# Power_Sheet.net
KiCad netlist of a schematic drawn in Altium Designer
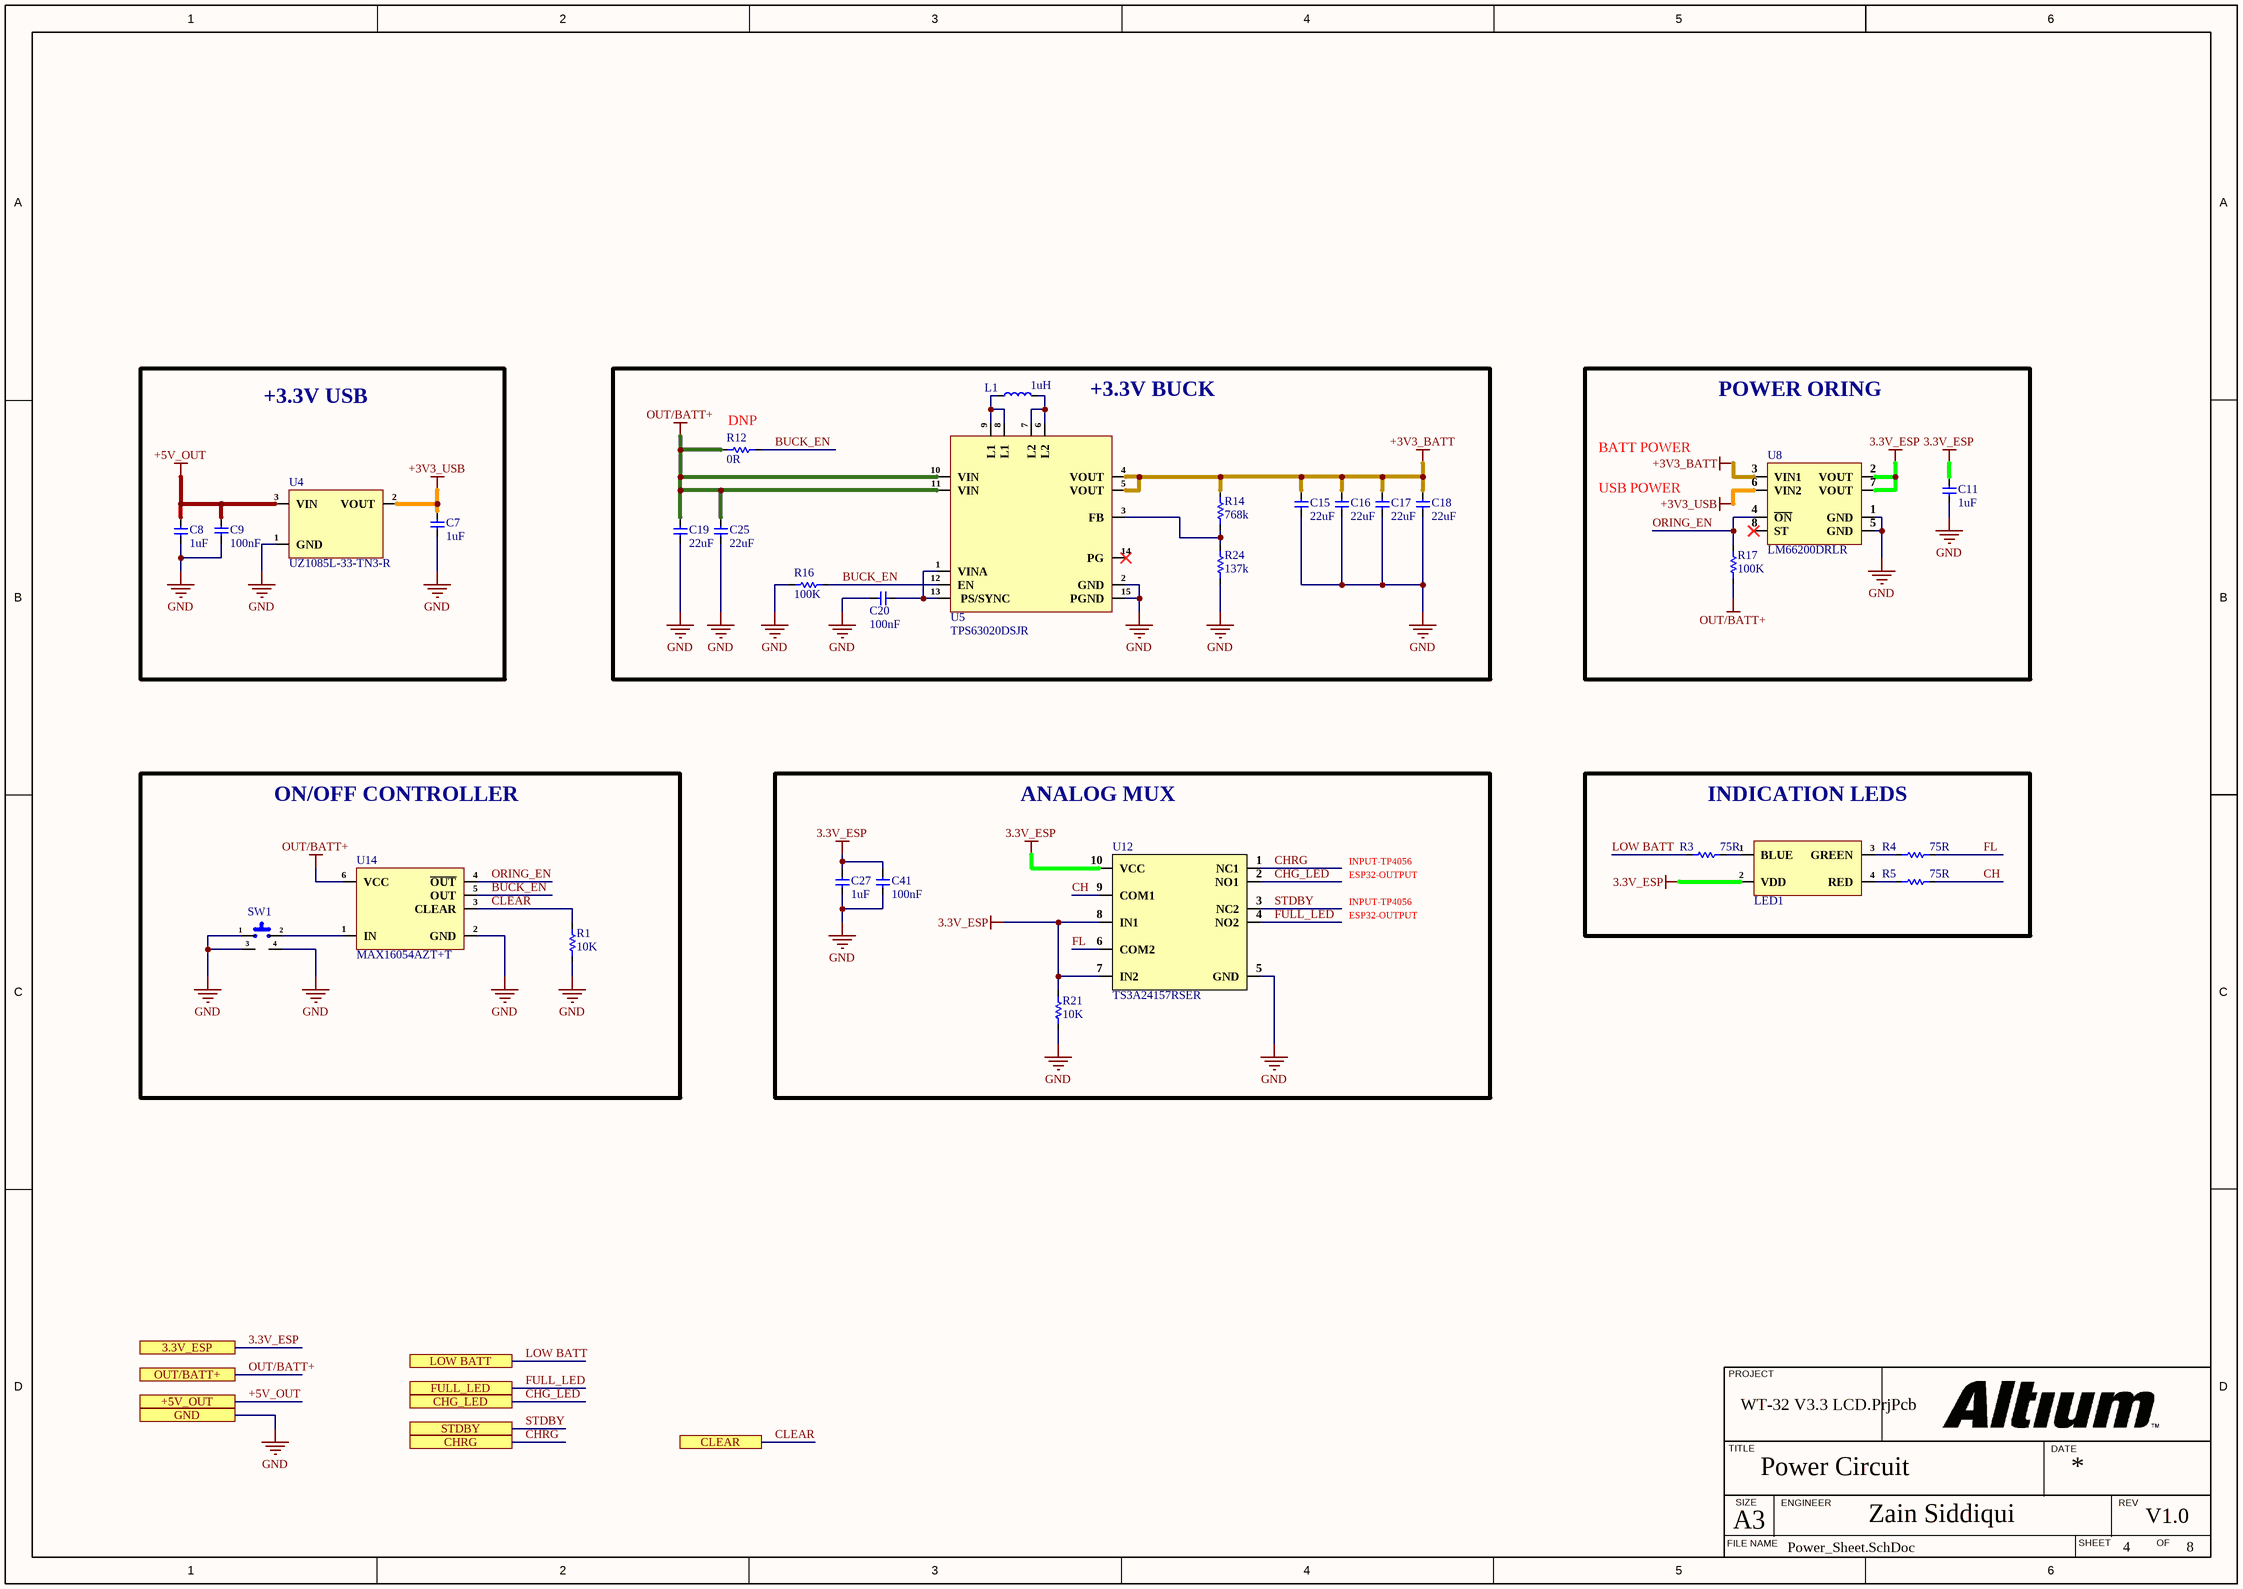
[diagram p0: Power_Sheet.SchDoc]

(export (version "E")
  (design (tool "Eeschema 10.0.6"))
  (components
    (comp (ref "C7")
      (value "1uF")
      (footprint "Cap-0402")
      (description "CAP CER 1UF 10V X5R 0402")
      (fields
        (field (name "MANUFACTURER") "Yageo")
        (field (name "MANUFACTURER PART NUMBER") "CC0402KRX5R6BB105")
      )
      (libsource (lib "eSpark Libraries") (part "CC0402KRX5R6BB105"))
    )
    (comp (ref "C8")
      (value "1uF")
      (footprint "Cap-0402")
      (description "CAP CER 1UF 25V X5R 0402")
      (fields
        (field (name "MANUFACTURER") "Yageo")
        (field (name "MANUFACTURER PART NUMBER") "CC0402KRX5R8BB105")
      )
      (libsource (lib "eSpark Libraries") (part "CC0402KRX5R8BB105"))
    )
    (comp (ref "C9")
      (value "100nF")
      (footprint "cap-0402")
      (description "CAP CER 0.1UF 50V X7R 0402")
      (fields
        (field (name "MANUFACTURER") "TDK")
        (field (name "MANUFACTURER PART NUMBER") "C1005X7R1H104KT000F")
      )
      (libsource (lib "eSpark Libraries") (part "C1005X7R1H104KT000F"))
    )
    (comp (ref "C11")
      (value "1uF")
      (footprint "Cap-0402")
      (description "CAP CER 1UF 25V X5R 0402")
      (fields
        (field (name "MANUFACTURER") "Yageo")
        (field (name "MANUFACTURER PART NUMBER") "CC0402KRX5R8BB105")
      )
      (libsource (lib "eSpark Libraries") (part "CC0402KRX5R8BB105"))
    )
    (comp (ref "C15")
      (value "22uF")
      (footprint "Cap-0805")
      (description "CAP CER 22UF 35V X5R 0805")
      (fields
        (field (name "MANUFACTURER") "TDK Corporation")
        (field (name "MANUFACTURER PART NUMBER") "C2012X5R1V226MT000E")
      )
      (libsource (lib "eSpark Libraries") (part "C2012X5R1V226MT000E"))
    )
    (comp (ref "C16")
      (value "22uF")
      (footprint "Cap-0805")
      (description "CAP CER 22UF 35V X5R 0805")
      (fields
        (field (name "MANUFACTURER") "TDK Corporation")
        (field (name "MANUFACTURER PART NUMBER") "C2012X5R1V226MT000E")
      )
      (libsource (lib "eSpark Libraries") (part "C2012X5R1V226MT000E"))
    )
    (comp (ref "C17")
      (value "22uF")
      (footprint "Cap-0805")
      (description "CAP CER 22UF 35V X5R 0805")
      (fields
        (field (name "MANUFACTURER") "TDK Corporation")
        (field (name "MANUFACTURER PART NUMBER") "C2012X5R1V226MT000E")
      )
      (libsource (lib "eSpark Libraries") (part "C2012X5R1V226MT000E"))
    )
    (comp (ref "C18")
      (value "22uF")
      (footprint "Cap-0805")
      (description "CAP CER 22UF 35V X5R 0805")
      (fields
        (field (name "MANUFACTURER") "TDK Corporation")
        (field (name "MANUFACTURER PART NUMBER") "C2012X5R1V226MT000E")
      )
      (libsource (lib "eSpark Libraries") (part "C2012X5R1V226MT000E"))
    )
    (comp (ref "C19")
      (value "22uF")
      (footprint "Cap-0805")
      (description "CAP CER 22UF 35V X5R 0805")
      (fields
        (field (name "MANUFACTURER") "TDK Corporation")
        (field (name "MANUFACTURER PART NUMBER") "C2012X5R1V226MT000E")
      )
      (libsource (lib "eSpark Libraries") (part "C2012X5R1V226MT000E"))
    )
    (comp (ref "C20")
      (value "100nF")
      (footprint "cap-0402")
      (description "CAP CER 0.1UF 50V X7R 0402")
      (fields
        (field (name "MANUFACTURER") "TDK")
        (field (name "MANUFACTURER PART NUMBER") "C1005X7R1H104KT000F")
      )
      (libsource (lib "eSpark Libraries") (part "C1005X7R1H104KT000F"))
    )
    (comp (ref "C25")
      (value "22uF")
      (footprint "Cap-0805")
      (description "CAP CER 22UF 35V X5R 0805")
      (fields
        (field (name "MANUFACTURER") "TDK Corporation")
        (field (name "MANUFACTURER PART NUMBER") "C2012X5R1V226MT000E")
      )
      (libsource (lib "eSpark Libraries") (part "C2012X5R1V226MT000E"))
    )
    (comp (ref "C27")
      (value "1uF")
      (footprint "Cap-0402")
      (description "CAP CER 1UF 25V X5R 0402")
      (fields
        (field (name "MANUFACTURER") "Yageo")
        (field (name "MANUFACTURER PART NUMBER") "CC0402KRX5R8BB105")
      )
      (libsource (lib "eSpark Libraries") (part "CC0402KRX5R8BB105"))
    )
    (comp (ref "C41")
      (value "100nF")
      (footprint "cap-0402")
      (description "CAP CER 0.1UF 50V X7R 0402")
      (fields
        (field (name "MANUFACTURER") "TDK")
        (field (name "MANUFACTURER PART NUMBER") "C1005X7R1H104KT000F")
      )
      (libsource (lib "eSpark Libraries") (part "C1005X7R1H104KT000F"))
    )
    (comp (ref "L1")
      (value "1uH")
      (footprint "IND-1008 (2520 Metric)")
      (description "FIXED IND 1UH 3.2A 0.042OHM SMD")
      (fields (field (name "LCSC PART NUMBER") "C882955") (field (name "MANUFACTURER") "Murata"))
      (libsource (lib "eSpark Libraries") (part "DFE252012P-1R0M=P2"))
    )
    (comp (ref "LED1")
      (value "S4-3528RGBTA-A")
      (footprint "SMD3528-4P")
      (description "SMD3528-4P LED Indication - Discrete RoHS")
      (fields (field (name "MANUFACTURER") "TUOZHAN") (field (name "LCSC PART NUMBER") "C2827321"))
      (libsource (lib "eSpark Libraries") (part "S4-3528RGBTA-A"))
    )
    (comp (ref "R1")
      (value "10K")
      (footprint "Res-0402")
      (description "RES 10K OHM 1% 1/16W 0402")
      (fields
        (field (name "MANUFACTURER") "Yageo")
        (field (name "MANUFACTURER PART NUMBER") "RC0402FR-0710KL")
      )
      (libsource (lib "eSpark Libraries") (part "RC0402FR-0710KL"))
    )
    (comp (ref "R3")
      (value "75R")
      (footprint "Res-0402")
      (description "75Ω ±1% 62.5mW 0402 Thick Film Resistor")
      (fields
        (field (name "MANUFACTURER") "YAGEO")
        (field (name "MANUFACTURER PART NUMBER") "RC0402FR-0775RL")
      )
      (libsource (lib "eSpark Libraries") (part "RC0402FR-0775RL"))
    )
    (comp (ref "R4")
      (value "75R")
      (footprint "Res-0402")
      (description "75Ω ±1% 62.5mW 0402 Thick Film Resistor")
      (fields
        (field (name "MANUFACTURER") "YAGEO")
        (field (name "MANUFACTURER PART NUMBER") "RC0402FR-0775RL")
      )
      (libsource (lib "eSpark Libraries") (part "RC0402FR-0775RL"))
    )
    (comp (ref "R5")
      (value "75R")
      (footprint "Res-0402")
      (description "75Ω ±1% 62.5mW 0402 Thick Film Resistor")
      (fields
        (field (name "MANUFACTURER") "YAGEO")
        (field (name "MANUFACTURER PART NUMBER") "RC0402FR-0775RL")
      )
      (libsource (lib "eSpark Libraries") (part "RC0402FR-0775RL"))
    )
    (comp (ref "R12")
      (value "0R")
      (footprint "Res-0402")
      (description "RES 0 OHM JUMPER 1/16W 0402")
      (fields
        (field (name "MANUFACTURER") "Yageo")
        (field (name "MANUFACTURER PART NUMBER") "RC0402FR-070RL")
      )
      (libsource (lib "eSpark Libraries") (part "RC0402FR-070RL"))
    )
    (comp (ref "R14")
      (value "768k")
      (footprint "Res-0402")
      (description "62.5mW Thick Film Resistor 50V ±100ppm/℃ ±1% 768kΩ 0402 Chip Resistor - Surface Mount ROHS")
      (fields
        (field (name "MANUFACTURER") "YAGEO")
        (field (name "MANUFACTURER PART NUMBER") "AC0402FR-07768KL")
      )
      (libsource (lib "eSpark Libraries") (part "AC0402FR-07768KL"))
    )
    (comp (ref "R16")
      (value "100K")
      (footprint "Res-0402")
      (description "RES SMD 100K OHM 0.1% 1/16W 0402")
      (fields
        (field (name "MANUFACTURER") "Yageo")
        (field (name "MANUFACTURER PART NUMBER") "RT0402BRD07100KL")
      )
      (libsource (lib "eSpark Libraries") (part "RT0402BRD07100KL"))
    )
    (comp (ref "R17")
      (value "100K")
      (footprint "Res-0402")
      (description "RES SMD 100K OHM 0.1% 1/16W 0402")
      (fields
        (field (name "MANUFACTURER") "Yageo")
        (field (name "MANUFACTURER PART NUMBER") "RT0402BRD07100KL")
      )
      (libsource (lib "eSpark Libraries") (part "RT0402BRD07100KL"))
    )
    (comp (ref "R21")
      (value "10K")
      (footprint "Res-0402")
      (description "RES 10K OHM 1% 1/16W 0402")
      (fields
        (field (name "MANUFACTURER") "Yageo")
        (field (name "MANUFACTURER PART NUMBER") "RC0402FR-0710KL")
      )
      (libsource (lib "eSpark Libraries") (part "RC0402FR-0710KL"))
    )
    (comp (ref "R24")
      (value "137k")
      (footprint "Res-0402")
      (description "62.5mW Thick Film Resistor 50V ±100ppm/℃ ±1% 137kΩ 0402 Chip Resistor - Surface Mount ROHS")
      (fields
        (field (name "MANUFACTURER") "FOJAN")
        (field (name "MANUFACTURER PART NUMBER") "FRC0402F1373TS")
      )
      (libsource (lib "eSpark Libraries") (part "FRC0402F1373TS"))
    )
    (comp (ref "SW1")
      (value "TC-6615-9.5-260G")
      (footprint "TC-6615-9.5-260G")
      (description "Tactile Switch SPST 260gf 9.5mm 6mm x 6mm Through Hole, Right Angle")
      (fields (field (name "MANUFACTURER") "HCTL") (field (name "LCSC PART NUMBER") "C2845278"))
      (libsource (lib "eSpark Libraries") (part "TC-6615-9.5-260G"))
    )
    (comp (ref "U4")
      (value "UZ1085L-33-TN3-R")
      (footprint "TO-252-2(DPAK)")
      (fields (field (name "MANUFACTURER") "UTC") (field (name "LCSC PART NUMBER") "C125622"))
      (libsource (lib "eSpark Libraries") (part "UZ1085L-33-TN3-R"))
    )
    (comp (ref "U5")
      (value "TPS63020DSJR")
      (footprint "14-VSON (4x3)")
      (description "IC REG BUCK-BST ADJ 3.5A 14VSON")
      (fields (field (name "MANUFACTURER") "Texas Instruments") (field (name "LCSC PART NUMBER") "C15483"))
      (libsource (lib "eSpark Libraries") (part "TPS63020DSJR"))
    )
    (comp (ref "U8")
      (value "LM66200DRLR")
      (footprint "SOT8")
      (description "1.6V to 5V, 2.5A dual ideal diodes with automatic switching function")
      (fields (field (name "MANUFACTURER") "TI") (field (name "LCSC PART NUMBER") "C3235556"))
      (libsource (lib "eSpark Libraries") (part "LM66200DRLR"))
    )
    (comp (ref "U12")
      (value "TS3A24157RSER")
      (footprint "UQFN-10(1.5x2)")
      (description "IC SWITCH DUAL SPDT 10UQFN")
      (fields (field (name "MANUFACTURER") "TI") (field (name "LCSC PART NUMBER") "C575568"))
      (libsource (lib "eSpark Libraries") (part "TS3A24157RSER"))
    )
    (comp (ref "U14")
      (value "MAX16054AZT+T")
      (footprint "TSOT-23-6")
      (description "IC CNTRLR ON/OFF W/DEB TSOT23-6")
      (fields (field (name "MANUFACTURER") "Maxim") (field (name "LCSC PART NUMBER") "C79401"))
      (libsource (lib "eSpark Libraries") (part "MAX16054AZT+T"))
    )
  )
  (nets
    (net (code "1") (name "+3V3_BATT") (class "Default")
      (node (ref "C15") (pin "2") (pinfunction "2_2") (pintype "passive"))
      (node (ref "C16") (pin "2") (pinfunction "2_2") (pintype "passive"))
      (node (ref "C17") (pin "2") (pinfunction "2_2") (pintype "passive"))
      (node (ref "C18") (pin "2") (pinfunction "2_2") (pintype "passive"))
      (node (ref "R14") (pin "2") (pinfunction "2_2") (pintype "passive"))
      (node (ref "U5") (pin "4") (pinfunction "VOUT_4") (pintype "passive"))
      (node (ref "U5") (pin "5") (pinfunction "VOUT_5") (pintype "passive"))
      (node (ref "U8") (pin "3") (pinfunction "VIN1_3") (pintype "passive"))
    )
    (net (code "2") (name "+3V3_USB") (class "Default")
      (node (ref "C7") (pin "2") (pinfunction "2_2") (pintype "passive"))
      (node (ref "U4") (pin "2") (pinfunction "VOUT_2") (pintype "passive"))
      (node (ref "U8") (pin "6") (pinfunction "VIN2_6") (pintype "passive"))
    )
    (net (code "3") (name "+5V_OUT") (class "Default")
      (node (ref "C8") (pin "2") (pinfunction "2_2") (pintype "passive"))
      (node (ref "C9") (pin "1") (pinfunction "1_1") (pintype "passive"))
      (node (ref "U4") (pin "3") (pinfunction "VIN_3") (pintype "passive"))
    )
    (net (code "4") (name "/BUCK_EN") (class "Default")
      (node (ref "R12") (pin "2") (pinfunction "2_2") (pintype "passive"))
      (node (ref "R16") (pin "2") (pinfunction "2_2") (pintype "passive"))
      (node (ref "U14") (pin "5") (pinfunction "OUT_5") (pintype "passive"))
      (node (ref "U5") (pin "12") (pinfunction "EN_12") (pintype "passive"))
    )
    (net (code "5") (name "/CH") (class "Default")
      (node (ref "R5") (pin "2") (pinfunction "2_2") (pintype "passive"))
      (node (ref "U12") (pin "9") (pinfunction "COM1_9") (pintype "passive"))
    )
    (net (code "6") (name "/CHG_LED") (class "Default")
      (node (ref "U12") (pin "2") (pinfunction "NO1_2") (pintype "passive"))
    )
    (net (code "7") (name "/CHRG") (class "Default")
      (node (ref "U12") (pin "1") (pinfunction "NC1_1") (pintype "passive"))
    )
    (net (code "8") (name "/CLEAR") (class "Default")
      (node (ref "R1") (pin "1") (pinfunction "1_1") (pintype "passive"))
      (node (ref "U14") (pin "3") (pinfunction "CLEAR_3") (pintype "passive"))
    )
    (net (code "9") (name "/FL") (class "Default")
      (node (ref "R4") (pin "2") (pinfunction "2_2") (pintype "passive"))
      (node (ref "U12") (pin "6") (pinfunction "COM2_6") (pintype "passive"))
    )
    (net (code "10") (name "/FULL_LED") (class "Default")
      (node (ref "U12") (pin "4") (pinfunction "NO2_4") (pintype "passive"))
    )
    (net (code "11") (name "/LOW BATT") (class "Default")
      (node (ref "R3") (pin "1") (pinfunction "1_1") (pintype "passive"))
    )
    (net (code "12") (name "/ORING_EN") (class "Default")
      (node (ref "R17") (pin "2") (pinfunction "2_2") (pintype "passive"))
      (node (ref "U14") (pin "4") (pinfunction "~{OUT}_4") (pintype "passive"))
      (node (ref "U8") (pin "4") (pinfunction "~{ON}_4") (pintype "passive"))
    )
    (net (code "13") (name "/STDBY") (class "Default")
      (node (ref "U12") (pin "3") (pinfunction "NC2_3") (pintype "passive"))
    )
    (net (code "14") (name "3.3V_ESP") (class "Default")
      (node (ref "C11") (pin "2") (pinfunction "2_2") (pintype "passive"))
      (node (ref "C27") (pin "2") (pinfunction "2_2") (pintype "passive"))
      (node (ref "C41") (pin "2") (pinfunction "2_2") (pintype "passive"))
      (node (ref "LED1") (pin "2") (pinfunction "VDD_2") (pintype "passive"))
      (node (ref "R21") (pin "1") (pinfunction "1_1") (pintype "passive"))
      (node (ref "U12") (pin "10") (pinfunction "VCC_10") (pintype "power_in"))
      (node (ref "U12") (pin "7") (pinfunction "IN2_7") (pintype "passive"))
      (node (ref "U12") (pin "8") (pinfunction "IN1_8") (pintype "passive"))
      (node (ref "U8") (pin "2") (pinfunction "VOUT_2") (pintype "passive"))
      (node (ref "U8") (pin "7") (pinfunction "VOUT_7") (pintype "passive"))
    )
    (net (code "15") (name "GND") (class "Default")
      (node (ref "C11") (pin "1") (pinfunction "1_1") (pintype "passive"))
      (node (ref "C15") (pin "1") (pinfunction "1_1") (pintype "passive"))
      (node (ref "C16") (pin "1") (pinfunction "1_1") (pintype "passive"))
      (node (ref "C17") (pin "1") (pinfunction "1_1") (pintype "passive"))
      (node (ref "C18") (pin "1") (pinfunction "1_1") (pintype "passive"))
      (node (ref "C19") (pin "1") (pinfunction "1_1") (pintype "passive"))
      (node (ref "C20") (pin "2") (pinfunction "2_2") (pintype "passive"))
      (node (ref "C25") (pin "1") (pinfunction "1_1") (pintype "passive"))
      (node (ref "C27") (pin "1") (pinfunction "1_1") (pintype "passive"))
      (node (ref "C41") (pin "1") (pinfunction "1_1") (pintype "passive"))
      (node (ref "C7") (pin "1") (pinfunction "1_1") (pintype "passive"))
      (node (ref "C8") (pin "1") (pinfunction "1_1") (pintype "passive"))
      (node (ref "C9") (pin "2") (pinfunction "2_2") (pintype "passive"))
      (node (ref "R1") (pin "2") (pinfunction "2_2") (pintype "passive"))
      (node (ref "R16") (pin "1") (pinfunction "1_1") (pintype "passive"))
      (node (ref "R21") (pin "2") (pinfunction "2_2") (pintype "passive"))
      (node (ref "R24") (pin "1") (pinfunction "1_1") (pintype "passive"))
      (node (ref "SW1") (pin "1") (pinfunction "1_1") (pintype "passive"))
      (node (ref "SW1") (pin "3") (pinfunction "3_3") (pintype "passive"))
      (node (ref "SW1") (pin "4") (pinfunction "4_4") (pintype "passive"))
      (node (ref "U12") (pin "5") (pinfunction "GND_5") (pintype "power_in"))
      (node (ref "U14") (pin "2") (pinfunction "GND_2") (pintype "passive"))
      (node (ref "U4") (pin "1") (pinfunction "GND_1") (pintype "passive"))
      (node (ref "U5") (pin "15") (pinfunction "PGND_15") (pintype "passive"))
      (node (ref "U5") (pin "2") (pinfunction "GND_2") (pintype "passive"))
      (node (ref "U8") (pin "1") (pinfunction "GND_1") (pintype "passive"))
      (node (ref "U8") (pin "5") (pinfunction "GND_5") (pintype "passive"))
    )
    (net (code "16") (name "Net-(L1-Pad1)") (class "Default")
      (node (ref "L1") (pin "1") (pinfunction "1_1") (pintype "passive"))
      (node (ref "U5") (pin "8") (pinfunction "L1_8") (pintype "passive"))
      (node (ref "U5") (pin "9") (pinfunction "L1_9") (pintype "passive"))
    )
    (net (code "17") (name "Net-(L1-Pad2)") (class "Default")
      (node (ref "L1") (pin "2") (pinfunction "2_2") (pintype "passive"))
      (node (ref "U5") (pin "6") (pinfunction "L2_6") (pintype "passive"))
      (node (ref "U5") (pin "7") (pinfunction "L2_7") (pintype "passive"))
    )
    (net (code "18") (name "Net-(LED1-BLUE)") (class "Default")
      (node (ref "LED1") (pin "1") (pinfunction "BLUE_1") (pintype "passive"))
      (node (ref "R3") (pin "2") (pinfunction "2_2") (pintype "passive"))
    )
    (net (code "19") (name "Net-(LED1-GREEN)") (class "Default")
      (node (ref "LED1") (pin "3") (pinfunction "GREEN_3") (pintype "passive"))
      (node (ref "R4") (pin "1") (pinfunction "1_1") (pintype "passive"))
    )
    (net (code "20") (name "Net-(LED1-RED)") (class "Default")
      (node (ref "LED1") (pin "4") (pinfunction "RED_4") (pintype "passive"))
      (node (ref "R5") (pin "1") (pinfunction "1_1") (pintype "passive"))
    )
    (net (code "21") (name "Net-(U5-FB)") (class "Default")
      (node (ref "R14") (pin "1") (pinfunction "1_1") (pintype "passive"))
      (node (ref "R24") (pin "2") (pinfunction "2_2") (pintype "passive"))
      (node (ref "U5") (pin "3") (pinfunction "FB_3") (pintype "passive"))
    )
    (net (code "22") (name "Net-(U5-VINA)") (class "Default")
      (node (ref "C20") (pin "1") (pinfunction "1_1") (pintype "passive"))
      (node (ref "U5") (pin "1") (pinfunction "VINA_1") (pintype "passive"))
      (node (ref "U5") (pin "13") (pinfunction "_PS/SYNC_13") (pintype "passive"))
    )
    (net (code "23") (name "Net-(U14-IN)") (class "Default")
      (node (ref "SW1") (pin "2") (pinfunction "2_2") (pintype "passive"))
      (node (ref "U14") (pin "1") (pinfunction "IN_1") (pintype "passive"))
    )
    (net (code "24") (name "OUT{slash}BATT+") (class "Default")
      (node (ref "C19") (pin "2") (pinfunction "2_2") (pintype "passive"))
      (node (ref "C25") (pin "2") (pinfunction "2_2") (pintype "passive"))
      (node (ref "R12") (pin "1") (pinfunction "1_1") (pintype "passive"))
      (node (ref "R17") (pin "1") (pinfunction "1_1") (pintype "passive"))
      (node (ref "U14") (pin "6") (pinfunction "VCC_6") (pintype "passive"))
      (node (ref "U5") (pin "10") (pinfunction "VIN_10") (pintype "passive"))
      (node (ref "U5") (pin "11") (pinfunction "VIN_11") (pintype "passive"))
    )
    (net (code "25") (name "unconnected-(U5-PG-Pad14)") (class "Default")
      (node (ref "U5") (pin "14") (pinfunction "PG_14") (pintype "passive+no_connect"))
    )
    (net (code "26") (name "unconnected-(U8-ST-Pad8)") (class "Default")
      (node (ref "U8") (pin "8") (pinfunction "ST_8") (pintype "passive+no_connect"))
    )
  )
)
